# v1_2.net
KiCad netlist of a schematic drawn in Altium Designer
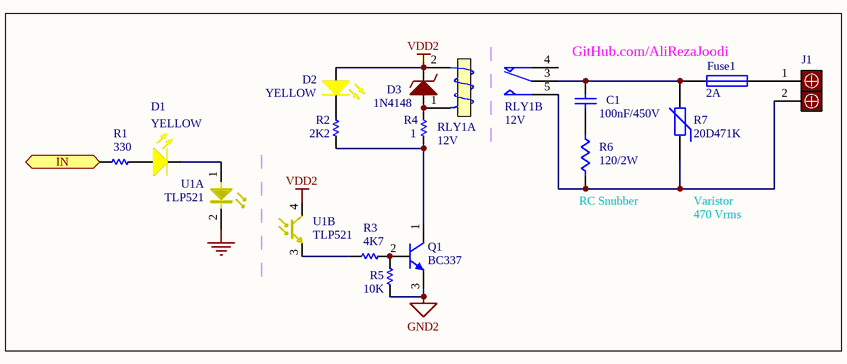
[diagram p0: v1.2.SchDoc]

(export (version "E")
  (design (tool "Eeschema 10.0.6"))
  (components
    (comp (ref "C1")
      (value "100nF/450V")
      (footprint "C_THD_CER_(P2.54-D3.5-T1.5)")
      (description "Capacitor, Ceramic Multilayer")
      (libsource (lib "Passive") (part "Capacitor_Ceramic"))
    )
    (comp (ref "D1")
      (value "YELLOW")
      (footprint "LED_THD_3MM_YELLOW_R")
      (description "LED, Yellow")
      (fields (field (name "MANUFACTURER") "Generic Components") (field (name "PUBLISHER") "Altium Limited"))
      (libsource (lib "Display") (part "LED_YELLOW"))
    )
    (comp (ref "D2")
      (value "YELLOW")
      (footprint "LED_THD_3MM_YELLOW_R")
      (description "LED, Yellow")
      (fields (field (name "MANUFACTURER") "Generic Components") (field (name "PUBLISHER") "Altium Limited"))
      (libsource (lib "Display") (part "LED_YELLOW"))
    )
    (comp (ref "D3")
      (value "1N4148")
      (footprint "D_THD_AXIAL0.3_DO-35")
      (description "Diode, Zener")
      (libsource (lib "Passive") (part "Diode_Zener"))
    )
    (comp (ref "Fuse1")
      (value "2A")
      (footprint "PIN-W2/E2.8")
      (description "Fuse")
      (fields (field (name "MANUFACTURER") "Generic Components") (field (name "PUBLISHER") "Altium Limited"))
      (libsource (lib "Miscellaneous Devices") (part "Fuse 1"))
    )
    (comp (ref "J1")
      (value "2PIN")
      (footprint "Connector_Phoenix_2PIN_MSTB")
      (description "Connector, Header, 2Pin")
      (libsource (lib "Connector") (part "Connector1x2_Power"))
    )
    (comp (ref "Q1")
      (value "BC337")
      (footprint "TO92C")
      (description "NPN Bipolar Transistor")
      (fields (field (name "MANUFACTURER") "Generic Components") (field (name "PUBLISHER") "Altium Limited"))
      (libsource (lib "Miscellaneous Devices") (part "NPN"))
    )
    (comp (ref "R1")
      (value "330")
      (footprint "R_THD_AXIAL0.4(1/4W)")
      (description "Resistor")
      (libsource (lib "Passive") (part "Resistor"))
    )
    (comp (ref "R2")
      (value "2K2")
      (footprint "R_THD_AXIAL0.4(1/4W)")
      (description "Resistor")
      (libsource (lib "Passive") (part "Resistor"))
    )
    (comp (ref "R3")
      (value "4K7")
      (footprint "R_THD_AXIAL0.4(1/4W)")
      (description "Resistor")
      (libsource (lib "Passive") (part "Resistor"))
    )
    (comp (ref "R4")
      (value "1")
      (footprint "R_THD_AXIAL0.4(1/4W)")
      (description "Resistor")
      (libsource (lib "Passive") (part "Resistor"))
    )
    (comp (ref "R5")
      (value "10K")
      (footprint "R_THD_AXIAL0.4(1/4W)")
      (description "Resistor")
      (libsource (lib "Passive") (part "Resistor"))
    )
    (comp (ref "R6")
      (value "120/2W")
      (footprint "R_THD_AXIAL0.4(1/4W)")
      (description "Resistor")
      (libsource (lib "Passive") (part "Resistor_3Form"))
    )
    (comp (ref "R7")
      (value "20D471K")
      (description "Varistor (Voltage-Sensitive Resistor)")
      (fields (field (name "MANUFACTURER") "Generic Components") (field (name "PUBLISHER") "Altium Limited"))
      (libsource (lib "Miscellaneous Devices") (part "Res Varistor"))
    )
    (comp (ref "RLY1")
      (value "12V")
      (footprint "RELAY_SPDT_5PIN_2216")
      (description "SPDT Relay")
      (libsource (lib "Passive") (part "Relay_SPDT_2Form"))
    )
    (comp (ref "U1")
      (value "TLP521")
      (footprint "DIP_4")
      (description "Optoisolator")
      (fields (field (name "PUBLISHER") "Altium Limited"))
      (libsource (lib "IC") (part "Optoisolator"))
    )
  )
  (nets
    (net (code "1") (name "/IN") (class "Default")
      (node (ref "R1") (pin "2") (pinfunction "2_2") (pintype "passive"))
    )
    (net (code "2") (name "GND") (class "Default")
      (node (ref "U1") (pin "2") (pinfunction "K_2") (pintype "power_in"))
    )
    (net (code "3") (name "GND2") (class "Default")
      (node (ref "Q1") (pin "3") (pinfunction "E_3") (pintype "passive"))
      (node (ref "R5") (pin "2") (pinfunction "2_2") (pintype "passive"))
    )
    (net (code "4") (name "Net-(C1-Pad1)") (class "Default")
      (node (ref "C1") (pin "1") (pinfunction "1_1") (pintype "passive"))
      (node (ref "R6") (pin "2") (pinfunction "2_2") (pintype "passive"))
    )
    (net (code "5") (name "Net-(D1-A)") (class "Default")
      (node (ref "D1") (pin "1") (pinfunction "A_1") (pintype "passive"))
      (node (ref "R1") (pin "1") (pinfunction "1_1") (pintype "passive"))
    )
    (net (code "6") (name "Net-(D1-K)") (class "Default")
      (node (ref "D1") (pin "2") (pinfunction "K_2") (pintype "passive"))
      (node (ref "U1") (pin "1") (pinfunction "A_1") (pintype "power_in"))
    )
    (net (code "7") (name "Net-(D2-K)") (class "Default")
      (node (ref "D2") (pin "2") (pinfunction "K_2") (pintype "passive"))
      (node (ref "R2") (pin "2") (pinfunction "2_2") (pintype "passive"))
    )
    (net (code "8") (name "Net-(Fuse1-Pad2)") (class "Default")
      (node (ref "Fuse1") (pin "2") (pinfunction "2_2") (pintype "passive"))
      (node (ref "J1") (pin "1") (pinfunction "1_1") (pintype "passive"))
    )
    (net (code "9") (name "Net-(Q1-B)") (class "Default")
      (node (ref "Q1") (pin "2") (pinfunction "B_2") (pintype "passive"))
      (node (ref "R3") (pin "1") (pinfunction "1_1") (pintype "passive"))
      (node (ref "R5") (pin "1") (pinfunction "1_1") (pintype "passive"))
    )
    (net (code "10") (name "Net-(Q1-C)") (class "Default")
      (node (ref "Q1") (pin "1") (pinfunction "C_1") (pintype "passive"))
      (node (ref "R2") (pin "1") (pinfunction "1_1") (pintype "passive"))
      (node (ref "R4") (pin "1") (pinfunction "1_1") (pintype "passive"))
    )
    (net (code "11") (name "Net-(RLY1A-T2)") (class "Default")
      (node (ref "D3") (pin "1") (pinfunction "1_1") (pintype "passive"))
      (node (ref "R4") (pin "2") (pinfunction "2_2") (pintype "passive"))
      (node (ref "RLY1") (pin "1") (pinfunction "T2_1") (pintype "passive"))
    )
    (net (code "12") (name "Net-(RLY1B-COM)") (class "Default")
      (node (ref "C1") (pin "2") (pinfunction "2_2") (pintype "passive"))
      (node (ref "Fuse1") (pin "1") (pinfunction "1_1") (pintype "passive"))
      (node (ref "R7") (pin "2") (pinfunction "2_2") (pintype "passive"))
      (node (ref "RLY1") (pin "3") (pinfunction "COM_3") (pintype "passive"))
    )
    (net (code "13") (name "Net-(RLY1B-NO)") (class "Default")
      (node (ref "J1") (pin "2") (pinfunction "2_2") (pintype "passive"))
      (node (ref "R6") (pin "1") (pinfunction "1_1") (pintype "passive"))
      (node (ref "R7") (pin "1") (pinfunction "1_1") (pintype "passive"))
      (node (ref "RLY1") (pin "5") (pinfunction "NO_5") (pintype "passive"))
    )
    (net (code "14") (name "Net-(U1B-E)") (class "Default")
      (node (ref "R3") (pin "2") (pinfunction "2_2") (pintype "passive"))
      (node (ref "U1") (pin "3") (pinfunction "E_3") (pintype "passive"))
    )
    (net (code "15") (name "VDD2") (class "Default")
      (node (ref "D2") (pin "1") (pinfunction "A_1") (pintype "passive"))
      (node (ref "D3") (pin "2") (pinfunction "2_2") (pintype "passive"))
      (node (ref "RLY1") (pin "2") (pinfunction "T1_2") (pintype "passive"))
      (node (ref "U1") (pin "4") (pinfunction "C_4") (pintype "passive"))
    )
    (net (code "16") (name "unconnected-(RLY1B-NC-Pad4)") (class "Default")
      (node (ref "RLY1") (pin "4") (pinfunction "NC_4") (pintype "passive"))
    )
  )
)
